# StepperSynth2_4_Motor.net
KiCad netlist of a schematic drawn in EAGLE
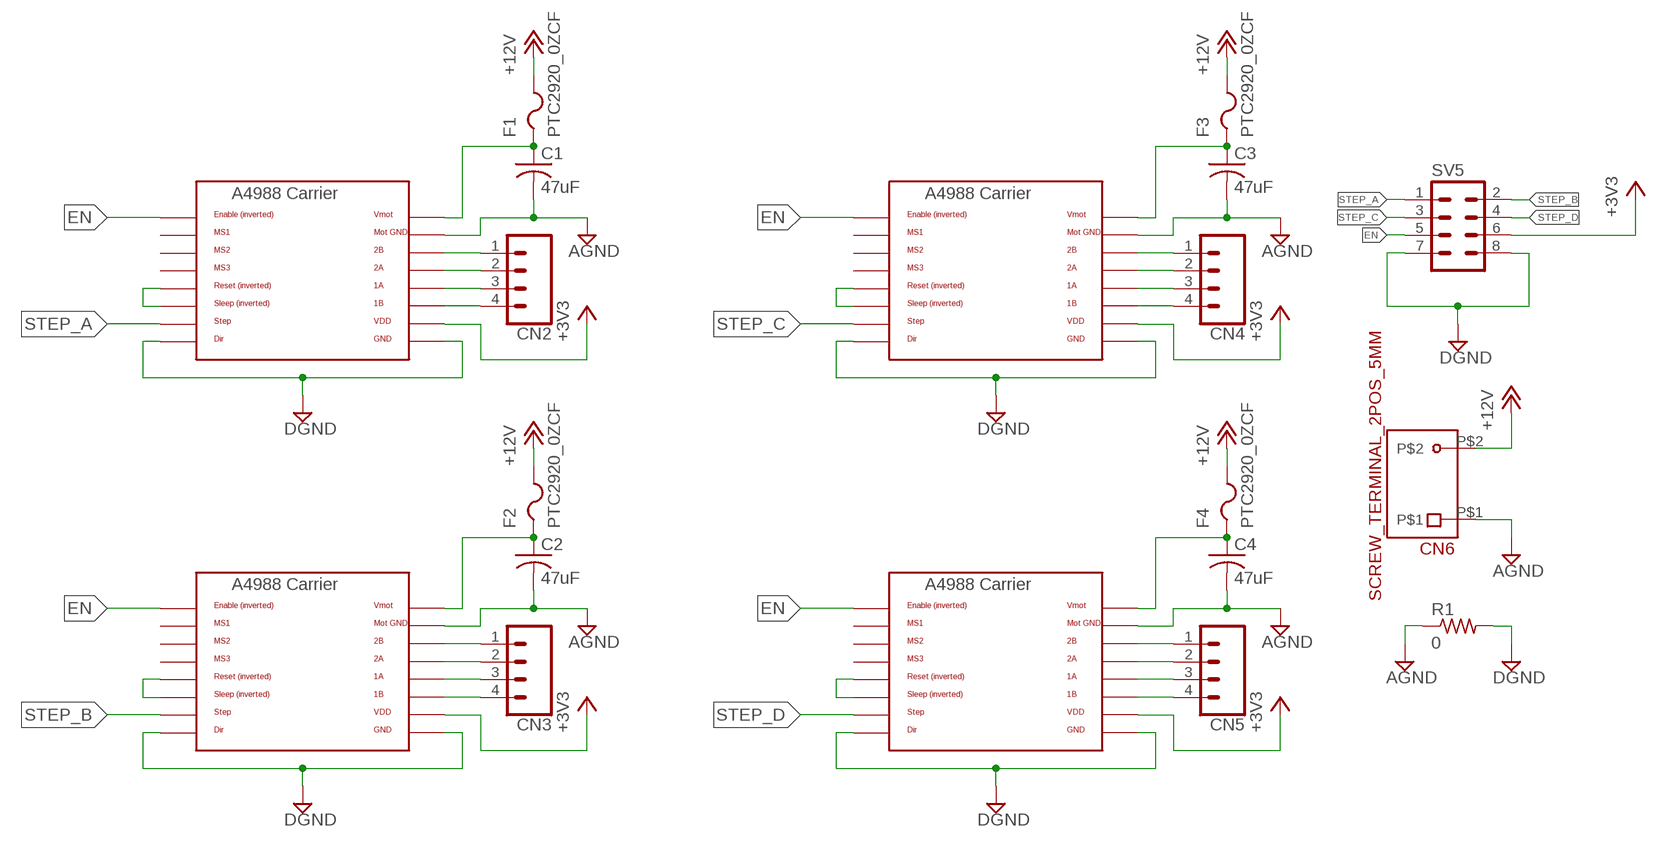
[diagram p0: schematic, sheet 1]

(export (version "E")
  (design (tool "Eeschema 10.0.6"))
  (components
    (comp (ref "C1")
      (value "47uF")
      (footprint "eagle-import:E5-10")
      (libsource (lib "eagle-import") (part "C_US_5_10"))
    )
    (comp (ref "C2")
      (value "47uF")
      (footprint "eagle-import:E5-10")
      (libsource (lib "eagle-import") (part "C_US_5_10"))
    )
    (comp (ref "C3")
      (value "47uF")
      (footprint "eagle-import:E5-10")
      (libsource (lib "eagle-import") (part "C_US_5_10"))
    )
    (comp (ref "C4")
      (value "47uF")
      (footprint "eagle-import:E5-10")
      (libsource (lib "eagle-import") (part "C_US_5_10"))
    )
    (comp (ref "CN2")
      (value "CONN_04_LOCK")
      (footprint "eagle-import:1X04_LOCK_LONGPADS")
      (libsource (lib "eagle-import") (part "CONN_04_LOCK"))
    )
    (comp (ref "CN3")
      (value "CONN_04_LOCK")
      (footprint "eagle-import:1X04_LOCK_LONGPADS")
      (libsource (lib "eagle-import") (part "CONN_04_LOCK"))
    )
    (comp (ref "CN4")
      (value "CONN_04_LOCK")
      (footprint "eagle-import:1X04_LOCK_LONGPADS")
      (libsource (lib "eagle-import") (part "CONN_04_LOCK"))
    )
    (comp (ref "CN5")
      (value "CONN_04_LOCK")
      (footprint "eagle-import:1X04_LOCK_LONGPADS")
      (libsource (lib "eagle-import") (part "CONN_04_LOCK"))
    )
    (comp (ref "CN6")
      (value "SCREW_TERMINAL_2POS_5MM")
      (footprint "eagle-import:2_POS_SCREW_TERM")
      (libsource (lib "eagle-import") (part "SCREW_TERMINAL_2POS_5MM"))
    )
    (comp (ref "F1")
      (value "PTC2920_0ZCF")
      (footprint "eagle-import:0ZCF")
      (fields (field (name "MANUFACTURER_PART_NUMBER") "0ZCF0150FF2C"))
      (libsource (lib "eagle-import") (part "PTC2920_0ZCF"))
    )
    (comp (ref "F2")
      (value "PTC2920_0ZCF")
      (footprint "eagle-import:0ZCF")
      (fields (field (name "MANUFACTURER_PART_NUMBER") "0ZCF0150FF2C"))
      (libsource (lib "eagle-import") (part "PTC2920_0ZCF"))
    )
    (comp (ref "F3")
      (value "PTC2920_0ZCF")
      (footprint "eagle-import:0ZCF")
      (fields (field (name "MANUFACTURER_PART_NUMBER") "0ZCF0150FF2C"))
      (libsource (lib "eagle-import") (part "PTC2920_0ZCF"))
    )
    (comp (ref "F4")
      (value "PTC2920_0ZCF")
      (footprint "eagle-import:0ZCF")
      (fields (field (name "MANUFACTURER_PART_NUMBER") "0ZCF0150FF2C"))
      (libsource (lib "eagle-import") (part "PTC2920_0ZCF"))
    )
    (comp (ref "R1")
      (value "0")
      (footprint "eagle-import:0207_15")
      (libsource (lib "eagle-import") (part "R-US_0207/15"))
    )
    (comp (ref "SV5")
      (value "CONN_4X2_LOCK4X2_LOCK")
      (footprint "eagle-import:CONN_4X2_LOCK")
      (libsource (lib "eagle-import") (part "CONN_4X2_LOCK4X2_LOCK"))
    )
    (comp (ref "U$1")
      (value "A4988BREAKOUT")
      (footprint "eagle-import:A4988BREAKOUT")
      (libsource (lib "eagle-import") (part "A4988BREAKOUT"))
    )
    (comp (ref "U$2")
      (value "A4988BREAKOUT")
      (footprint "eagle-import:A4988BREAKOUT")
      (libsource (lib "eagle-import") (part "A4988BREAKOUT"))
    )
    (comp (ref "U$3")
      (value "A4988BREAKOUT")
      (footprint "eagle-import:A4988BREAKOUT")
      (libsource (lib "eagle-import") (part "A4988BREAKOUT"))
    )
    (comp (ref "U$4")
      (value "A4988BREAKOUT")
      (footprint "eagle-import:A4988BREAKOUT")
      (libsource (lib "eagle-import") (part "A4988BREAKOUT"))
    )
  )
  (nets
    (net (code "1") (name "+3V3") (class "Default")
      (node (ref "SV5") (pin "6") (pinfunction "6_6") (pintype "passive"))
      (node (ref "U$1") (pin "VDD") (pinfunction "VDD_VDD") (pintype "power_in"))
      (node (ref "U$2") (pin "VDD") (pinfunction "VDD_VDD") (pintype "power_in"))
      (node (ref "U$3") (pin "VDD") (pinfunction "VDD_VDD") (pintype "power_in"))
      (node (ref "U$4") (pin "VDD") (pinfunction "VDD_VDD") (pintype "power_in"))
    )
    (net (code "2") (name "+12V") (class "Default")
      (node (ref "CN6") (pin "P$2") (pinfunction "P$2_P$2") (pintype "bidirectional"))
      (node (ref "F1") (pin "2") (pinfunction "2_2") (pintype "passive"))
      (node (ref "F2") (pin "2") (pinfunction "2_2") (pintype "passive"))
      (node (ref "F3") (pin "2") (pinfunction "2_2") (pintype "passive"))
      (node (ref "F4") (pin "2") (pinfunction "2_2") (pintype "passive"))
    )
    (net (code "3") (name "AGND") (class "Default")
      (node (ref "C1") (pin "-") (pinfunction "-_-") (pintype "passive"))
      (node (ref "C2") (pin "-") (pinfunction "-_-") (pintype "passive"))
      (node (ref "C3") (pin "-") (pinfunction "-_-") (pintype "passive"))
      (node (ref "C4") (pin "-") (pinfunction "-_-") (pintype "passive"))
      (node (ref "CN6") (pin "P$1") (pinfunction "P$1_P$1") (pintype "bidirectional"))
      (node (ref "R1") (pin "1") (pinfunction "1_1") (pintype "passive"))
      (node (ref "U$1") (pin "MOTGND") (pinfunction "MOTGND_MOTGND") (pintype "power_in"))
      (node (ref "U$2") (pin "MOTGND") (pinfunction "MOTGND_MOTGND") (pintype "power_in"))
      (node (ref "U$3") (pin "MOTGND") (pinfunction "MOTGND_MOTGND") (pintype "power_in"))
      (node (ref "U$4") (pin "MOTGND") (pinfunction "MOTGND_MOTGND") (pintype "power_in"))
    )
    (net (code "4") (name "DGND") (class "Default")
      (node (ref "R1") (pin "2") (pinfunction "2_2") (pintype "passive"))
      (node (ref "SV5") (pin "7") (pinfunction "7_7") (pintype "passive"))
      (node (ref "SV5") (pin "8") (pinfunction "8_8") (pintype "passive"))
      (node (ref "U$1") (pin "DIR") (pinfunction "DIR_DIR") (pintype "input"))
      (node (ref "U$1") (pin "GND") (pinfunction "GND_GND") (pintype "power_in"))
      (node (ref "U$2") (pin "DIR") (pinfunction "DIR_DIR") (pintype "input"))
      (node (ref "U$2") (pin "GND") (pinfunction "GND_GND") (pintype "power_in"))
      (node (ref "U$3") (pin "DIR") (pinfunction "DIR_DIR") (pintype "input"))
      (node (ref "U$3") (pin "GND") (pinfunction "GND_GND") (pintype "power_in"))
      (node (ref "U$4") (pin "DIR") (pinfunction "DIR_DIR") (pintype "input"))
      (node (ref "U$4") (pin "GND") (pinfunction "GND_GND") (pintype "power_in"))
    )
    (net (code "5") (name "EN") (class "Default")
      (node (ref "SV5") (pin "5") (pinfunction "5_5") (pintype "passive"))
      (node (ref "U$1") (pin "EN") (pinfunction "EN_EN") (pintype "input"))
      (node (ref "U$2") (pin "EN") (pinfunction "EN_EN") (pintype "input"))
      (node (ref "U$3") (pin "EN") (pinfunction "EN_EN") (pintype "input"))
      (node (ref "U$4") (pin "EN") (pinfunction "EN_EN") (pintype "input"))
    )
    (net (code "6") (name "Net-(C1-Pad+)") (class "Default")
      (node (ref "C1") (pin "+") (pinfunction "+_+") (pintype "passive"))
      (node (ref "F1") (pin "1") (pinfunction "1_1") (pintype "passive"))
      (node (ref "U$1") (pin "VMOT") (pinfunction "VMOT_VMOT") (pintype "power_in"))
    )
    (net (code "7") (name "Net-(C2-Pad+)") (class "Default")
      (node (ref "C2") (pin "+") (pinfunction "+_+") (pintype "passive"))
      (node (ref "F2") (pin "1") (pinfunction "1_1") (pintype "passive"))
      (node (ref "U$2") (pin "VMOT") (pinfunction "VMOT_VMOT") (pintype "power_in"))
    )
    (net (code "8") (name "Net-(C3-Pad+)") (class "Default")
      (node (ref "C3") (pin "+") (pinfunction "+_+") (pintype "passive"))
      (node (ref "F3") (pin "1") (pinfunction "1_1") (pintype "passive"))
      (node (ref "U$3") (pin "VMOT") (pinfunction "VMOT_VMOT") (pintype "power_in"))
    )
    (net (code "9") (name "Net-(C4-Pad+)") (class "Default")
      (node (ref "C4") (pin "+") (pinfunction "+_+") (pintype "passive"))
      (node (ref "F4") (pin "1") (pinfunction "1_1") (pintype "passive"))
      (node (ref "U$4") (pin "VMOT") (pinfunction "VMOT_VMOT") (pintype "power_in"))
    )
    (net (code "10") (name "Net-(CN2-Pad1)") (class "Default")
      (node (ref "CN2") (pin "1") (pinfunction "1_1") (pintype "passive"))
      (node (ref "U$1") (pin "2B") (pinfunction "2B_2B") (pintype "output"))
    )
    (net (code "11") (name "Net-(CN2-Pad2)") (class "Default")
      (node (ref "CN2") (pin "2") (pinfunction "2_2") (pintype "passive"))
      (node (ref "U$1") (pin "2A") (pinfunction "2A_2A") (pintype "output"))
    )
    (net (code "12") (name "Net-(CN2-Pad3)") (class "Default")
      (node (ref "CN2") (pin "3") (pinfunction "3_3") (pintype "passive"))
      (node (ref "U$1") (pin "1A") (pinfunction "1A_1A") (pintype "output"))
    )
    (net (code "13") (name "Net-(CN2-Pad4)") (class "Default")
      (node (ref "CN2") (pin "4") (pinfunction "4_4") (pintype "passive"))
      (node (ref "U$1") (pin "1B") (pinfunction "1B_1B") (pintype "output"))
    )
    (net (code "14") (name "Net-(CN3-Pad1)") (class "Default")
      (node (ref "CN3") (pin "1") (pinfunction "1_1") (pintype "passive"))
      (node (ref "U$2") (pin "2B") (pinfunction "2B_2B") (pintype "output"))
    )
    (net (code "15") (name "Net-(CN3-Pad2)") (class "Default")
      (node (ref "CN3") (pin "2") (pinfunction "2_2") (pintype "passive"))
      (node (ref "U$2") (pin "2A") (pinfunction "2A_2A") (pintype "output"))
    )
    (net (code "16") (name "Net-(CN3-Pad3)") (class "Default")
      (node (ref "CN3") (pin "3") (pinfunction "3_3") (pintype "passive"))
      (node (ref "U$2") (pin "1A") (pinfunction "1A_1A") (pintype "output"))
    )
    (net (code "17") (name "Net-(CN3-Pad4)") (class "Default")
      (node (ref "CN3") (pin "4") (pinfunction "4_4") (pintype "passive"))
      (node (ref "U$2") (pin "1B") (pinfunction "1B_1B") (pintype "output"))
    )
    (net (code "18") (name "Net-(CN4-Pad1)") (class "Default")
      (node (ref "CN4") (pin "1") (pinfunction "1_1") (pintype "passive"))
      (node (ref "U$3") (pin "2B") (pinfunction "2B_2B") (pintype "output"))
    )
    (net (code "19") (name "Net-(CN4-Pad2)") (class "Default")
      (node (ref "CN4") (pin "2") (pinfunction "2_2") (pintype "passive"))
      (node (ref "U$3") (pin "2A") (pinfunction "2A_2A") (pintype "output"))
    )
    (net (code "20") (name "Net-(CN4-Pad3)") (class "Default")
      (node (ref "CN4") (pin "3") (pinfunction "3_3") (pintype "passive"))
      (node (ref "U$3") (pin "1A") (pinfunction "1A_1A") (pintype "output"))
    )
    (net (code "21") (name "Net-(CN4-Pad4)") (class "Default")
      (node (ref "CN4") (pin "4") (pinfunction "4_4") (pintype "passive"))
      (node (ref "U$3") (pin "1B") (pinfunction "1B_1B") (pintype "output"))
    )
    (net (code "22") (name "Net-(CN5-Pad1)") (class "Default")
      (node (ref "CN5") (pin "1") (pinfunction "1_1") (pintype "passive"))
      (node (ref "U$4") (pin "2B") (pinfunction "2B_2B") (pintype "output"))
    )
    (net (code "23") (name "Net-(CN5-Pad2)") (class "Default")
      (node (ref "CN5") (pin "2") (pinfunction "2_2") (pintype "passive"))
      (node (ref "U$4") (pin "2A") (pinfunction "2A_2A") (pintype "output"))
    )
    (net (code "24") (name "Net-(CN5-Pad3)") (class "Default")
      (node (ref "CN5") (pin "3") (pinfunction "3_3") (pintype "passive"))
      (node (ref "U$4") (pin "1A") (pinfunction "1A_1A") (pintype "output"))
    )
    (net (code "25") (name "Net-(CN5-Pad4)") (class "Default")
      (node (ref "CN5") (pin "4") (pinfunction "4_4") (pintype "passive"))
      (node (ref "U$4") (pin "1B") (pinfunction "1B_1B") (pintype "output"))
    )
    (net (code "26") (name "Net-(U$1-SLEEP)") (class "Default")
      (node (ref "U$1") (pin "RST") (pinfunction "RST_RST") (pintype "input"))
      (node (ref "U$1") (pin "SLP") (pinfunction "SLEEP_SLP") (pintype "input"))
    )
    (net (code "27") (name "Net-(U$2-SLEEP)") (class "Default")
      (node (ref "U$2") (pin "RST") (pinfunction "RST_RST") (pintype "input"))
      (node (ref "U$2") (pin "SLP") (pinfunction "SLEEP_SLP") (pintype "input"))
    )
    (net (code "28") (name "Net-(U$3-SLEEP)") (class "Default")
      (node (ref "U$3") (pin "RST") (pinfunction "RST_RST") (pintype "input"))
      (node (ref "U$3") (pin "SLP") (pinfunction "SLEEP_SLP") (pintype "input"))
    )
    (net (code "29") (name "Net-(U$4-SLEEP)") (class "Default")
      (node (ref "U$4") (pin "RST") (pinfunction "RST_RST") (pintype "input"))
      (node (ref "U$4") (pin "SLP") (pinfunction "SLEEP_SLP") (pintype "input"))
    )
    (net (code "30") (name "STEP_A") (class "Default")
      (node (ref "SV5") (pin "1") (pinfunction "1_1") (pintype "passive"))
      (node (ref "U$1") (pin "STEP") (pinfunction "STEP_STEP") (pintype "input"))
    )
    (net (code "31") (name "STEP_B") (class "Default")
      (node (ref "SV5") (pin "2") (pinfunction "2_2") (pintype "passive"))
      (node (ref "U$2") (pin "STEP") (pinfunction "STEP_STEP") (pintype "input"))
    )
    (net (code "32") (name "STEP_C") (class "Default")
      (node (ref "SV5") (pin "3") (pinfunction "3_3") (pintype "passive"))
      (node (ref "U$3") (pin "STEP") (pinfunction "STEP_STEP") (pintype "input"))
    )
    (net (code "33") (name "STEP_D") (class "Default")
      (node (ref "SV5") (pin "4") (pinfunction "4_4") (pintype "passive"))
      (node (ref "U$4") (pin "STEP") (pinfunction "STEP_STEP") (pintype "input"))
    )
    (net (code "34") (name "unconnected-(U$1-PadMS1)") (class "Default")
      (node (ref "U$1") (pin "MS1") (pinfunction "MS1_MS1") (pintype "input"))
    )
    (net (code "35") (name "unconnected-(U$1-PadMS2)") (class "Default")
      (node (ref "U$1") (pin "MS2") (pinfunction "MS2_MS2") (pintype "input"))
    )
    (net (code "36") (name "unconnected-(U$1-PadMS3)") (class "Default")
      (node (ref "U$1") (pin "MS3") (pinfunction "MS3_MS3") (pintype "input"))
    )
    (net (code "37") (name "unconnected-(U$2-PadMS1)") (class "Default")
      (node (ref "U$2") (pin "MS1") (pinfunction "MS1_MS1") (pintype "input"))
    )
    (net (code "38") (name "unconnected-(U$2-PadMS2)") (class "Default")
      (node (ref "U$2") (pin "MS2") (pinfunction "MS2_MS2") (pintype "input"))
    )
    (net (code "39") (name "unconnected-(U$2-PadMS3)") (class "Default")
      (node (ref "U$2") (pin "MS3") (pinfunction "MS3_MS3") (pintype "input"))
    )
    (net (code "40") (name "unconnected-(U$3-PadMS1)") (class "Default")
      (node (ref "U$3") (pin "MS1") (pinfunction "MS1_MS1") (pintype "input"))
    )
    (net (code "41") (name "unconnected-(U$3-PadMS2)") (class "Default")
      (node (ref "U$3") (pin "MS2") (pinfunction "MS2_MS2") (pintype "input"))
    )
    (net (code "42") (name "unconnected-(U$3-PadMS3)") (class "Default")
      (node (ref "U$3") (pin "MS3") (pinfunction "MS3_MS3") (pintype "input"))
    )
    (net (code "43") (name "unconnected-(U$4-PadMS1)") (class "Default")
      (node (ref "U$4") (pin "MS1") (pinfunction "MS1_MS1") (pintype "input"))
    )
    (net (code "44") (name "unconnected-(U$4-PadMS2)") (class "Default")
      (node (ref "U$4") (pin "MS2") (pinfunction "MS2_MS2") (pintype "input"))
    )
    (net (code "45") (name "unconnected-(U$4-PadMS3)") (class "Default")
      (node (ref "U$4") (pin "MS3") (pinfunction "MS3_MS3") (pintype "input"))
    )
  )
)
